# 04-OUTPUT.net
KiCad netlist of a schematic drawn in Altium Designer
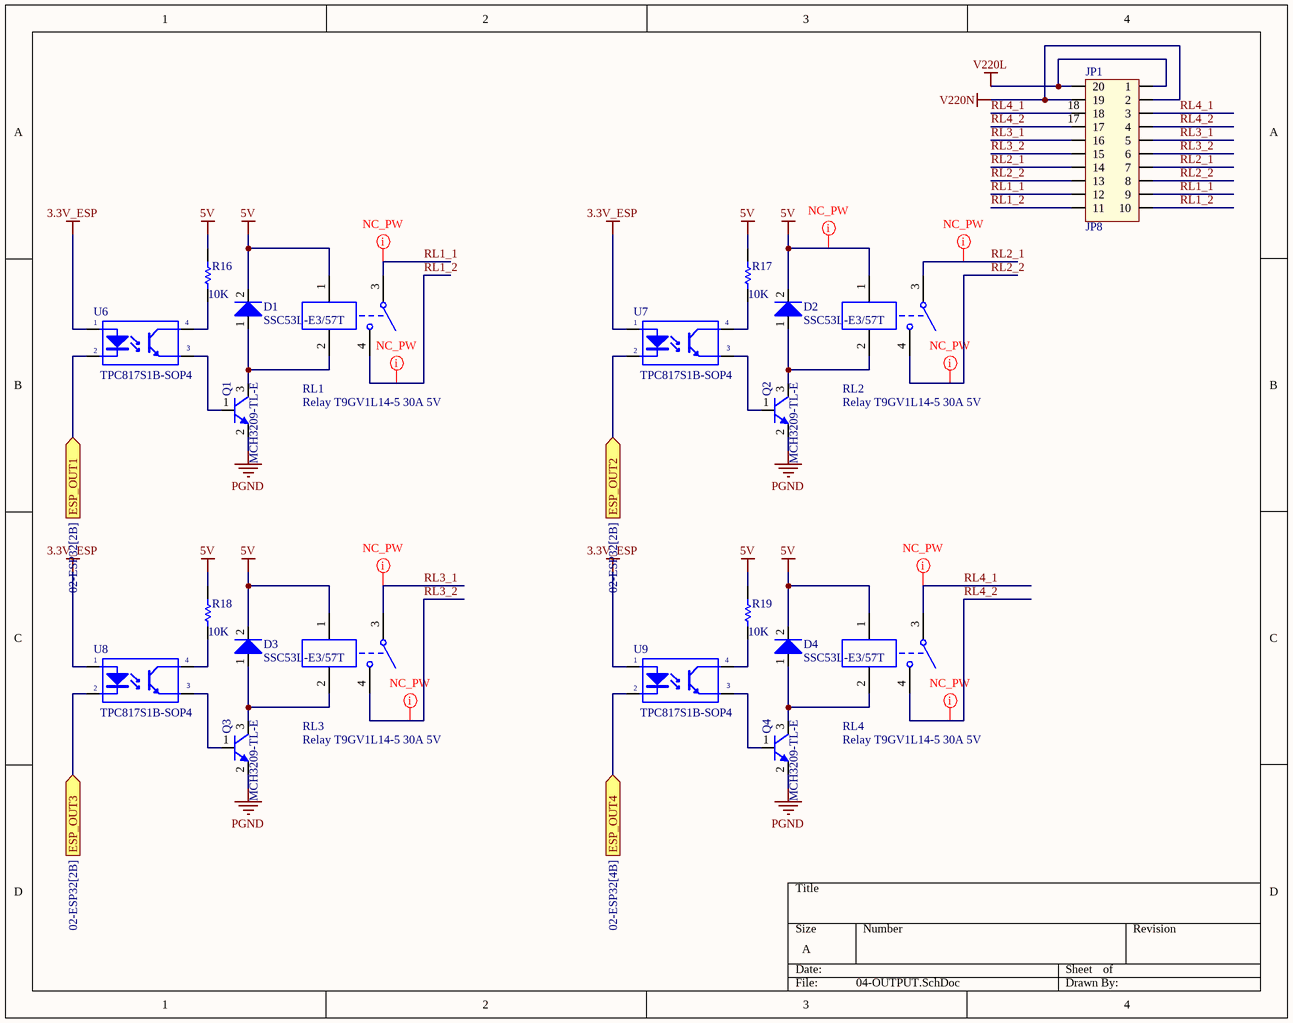
[diagram p0: 04-OUTPUT.SchDoc]

(export (version "E")
  (design (tool "Eeschema 10.0.6"))
  (components
    (comp (ref "D1")
      (value "SSC53L-E3/57T")
      (footprint "1n4007 smd DO214")
      (description "DIODE SCHOTTKY 30V 5A DO214AB")
      (libsource (lib "lpson") (part "10A10"))
    )
    (comp (ref "D2")
      (value "SSC53L-E3/57T")
      (footprint "1n4007 smd DO214")
      (description "DIODE SCHOTTKY 30V 5A DO214AB")
      (libsource (lib "lpson") (part "10A10"))
    )
    (comp (ref "D3")
      (value "SSC53L-E3/57T")
      (footprint "1n4007 smd DO214")
      (description "DIODE SCHOTTKY 30V 5A DO214AB")
      (libsource (lib "lpson") (part "10A10"))
    )
    (comp (ref "D4")
      (value "SSC53L-E3/57T")
      (footprint "1n4007 smd DO214")
      (description "DIODE SCHOTTKY 30V 5A DO214AB")
      (libsource (lib "lpson") (part "10A10"))
    )
    (comp (ref "JP1")
      (value "JP8")
      (footprint "KF142V 10PIN")
      (description "Terminal KF142 9pin")
      (libsource (lib "lpson") (part "Terminal KF142 10pin"))
    )
    (comp (ref "Q1")
      (value "MCH3209-TL-E")
      (footprint "MCH3209-TL-E  SOT-323")
      (description "Bipolar (BJT) Transistor NPN 30V 3A 450MHz 800mW Surface Mount 3-MCPH")
      (libsource (lib "lpson") (part "2SC1815"))
    )
    (comp (ref "Q2")
      (value "MCH3209-TL-E")
      (footprint "MCH3209-TL-E  SOT-323")
      (description "Bipolar (BJT) Transistor NPN 30V 3A 450MHz 800mW Surface Mount 3-MCPH")
      (libsource (lib "lpson") (part "2SC1815"))
    )
    (comp (ref "Q3")
      (value "MCH3209-TL-E")
      (footprint "MCH3209-TL-E  SOT-323")
      (description "Bipolar (BJT) Transistor NPN 30V 3A 450MHz 800mW Surface Mount 3-MCPH")
      (libsource (lib "lpson") (part "2SC1815"))
    )
    (comp (ref "Q4")
      (value "MCH3209-TL-E")
      (footprint "MCH3209-TL-E  SOT-323")
      (description "Bipolar (BJT) Transistor NPN 30V 3A 450MHz 800mW Surface Mount 3-MCPH")
      (libsource (lib "lpson") (part "2SC1815"))
    )
    (comp (ref "R16")
      (value "10K")
      (footprint "Res 0805 SMD")
      (description "RES SMD 249K OHM 1% 1/10W 0805")
      (fields
        (field (name "MANUFACTURER") "Yageo")
        (field (name "MANUFACTURER PART NUMBER") "RC0603FR-07249KL")
      )
      (libsource (lib "GSHT_181013") (part "249K/R0805/1%"))
    )
    (comp (ref "R17")
      (value "10K")
      (footprint "Res 0805 SMD")
      (description "RES SMD 249K OHM 1% 1/10W 0805")
      (fields
        (field (name "MANUFACTURER") "Yageo")
        (field (name "MANUFACTURER PART NUMBER") "RC0603FR-07249KL")
      )
      (libsource (lib "GSHT_181013") (part "249K/R0805/1%"))
    )
    (comp (ref "R18")
      (value "10K")
      (footprint "Res 0805 SMD")
      (description "RES SMD 249K OHM 1% 1/10W 0805")
      (fields
        (field (name "MANUFACTURER") "Yageo")
        (field (name "MANUFACTURER PART NUMBER") "RC0603FR-07249KL")
      )
      (libsource (lib "GSHT_181013") (part "249K/R0805/1%"))
    )
    (comp (ref "R19")
      (value "10K")
      (footprint "Res 0805 SMD")
      (description "RES SMD 249K OHM 1% 1/10W 0805")
      (fields
        (field (name "MANUFACTURER") "Yageo")
        (field (name "MANUFACTURER PART NUMBER") "RC0603FR-07249KL")
      )
      (libsource (lib "GSHT_181013") (part "249K/R0805/1%"))
    )
    (comp (ref "RL1")
      (value "Relay T9GV1L14-5 30A 5V")
      (footprint "RELAY_PA1A_PAN")
      (description "General Purpose Relay SPST-NO (1 Form A) 5VDC Coil Through Hole")
      (libsource (lib "PCB_ESP32_RFID") (part "Relay T9GV1L14-5 30A 5V"))
    )
    (comp (ref "RL2")
      (value "Relay T9GV1L14-5 30A 5V")
      (footprint "RELAY_PA1A_PAN")
      (description "General Purpose Relay SPST-NO (1 Form A) 5VDC Coil Through Hole")
      (libsource (lib "PCB_ESP32_RFID") (part "Relay T9GV1L14-5 30A 5V"))
    )
    (comp (ref "RL3")
      (value "Relay T9GV1L14-5 30A 5V")
      (footprint "RELAY_PA1A_PAN")
      (description "General Purpose Relay SPST-NO (1 Form A) 5VDC Coil Through Hole")
      (libsource (lib "PCB_ESP32_RFID") (part "Relay T9GV1L14-5 30A 5V"))
    )
    (comp (ref "RL4")
      (value "Relay T9GV1L14-5 30A 5V")
      (footprint "RELAY_PA1A_PAN")
      (description "General Purpose Relay SPST-NO (1 Form A) 5VDC Coil Through Hole")
      (libsource (lib "PCB_ESP32_RFID") (part "Relay T9GV1L14-5 30A 5V"))
    )
    (comp (ref "U6")
      (value "TPC817S1B-SOP4")
      (footprint "TPC817-4SOP")
      (description "Optoisolator Transistor Output 5000Vrms 1 Channel 4-SOP")
      (libsource (lib "lpson") (part "PC817"))
    )
    (comp (ref "U7")
      (value "TPC817S1B-SOP4")
      (footprint "TPC817-4SOP")
      (description "Optoisolator Transistor Output 5000Vrms 1 Channel 4-SOP")
      (libsource (lib "lpson") (part "PC817"))
    )
    (comp (ref "U8")
      (value "TPC817S1B-SOP4")
      (footprint "TPC817-4SOP")
      (description "Optoisolator Transistor Output 5000Vrms 1 Channel 4-SOP")
      (libsource (lib "lpson") (part "PC817"))
    )
    (comp (ref "U9")
      (value "TPC817S1B-SOP4")
      (footprint "TPC817-4SOP")
      (description "Optoisolator Transistor Output 5000Vrms 1 Channel 4-SOP")
      (libsource (lib "lpson") (part "PC817"))
    )
  )
  (nets
    (net (code "1") (name "/ESP_OUT1") (class "Default")
      (node (ref "U6") (pin "2") (pinfunction "K_2") (pintype "passive"))
    )
    (net (code "2") (name "/ESP_OUT2") (class "Default")
      (node (ref "U7") (pin "2") (pinfunction "K_2") (pintype "passive"))
    )
    (net (code "3") (name "/ESP_OUT3") (class "Default")
      (node (ref "U8") (pin "2") (pinfunction "K_2") (pintype "passive"))
    )
    (net (code "4") (name "/ESP_OUT4") (class "Default")
      (node (ref "U9") (pin "2") (pinfunction "K_2") (pintype "passive"))
    )
    (net (code "5") (name "/RL1_1") (class "Default")
      (node (ref "JP1") (pin "12") (pinfunction "12_12") (pintype "passive"))
      (node (ref "JP1") (pin "9") (pinfunction "9_9") (pintype "passive"))
      (node (ref "RL1") (pin "3") (pinfunction "3_3") (pintype "passive"))
    )
    (net (code "6") (name "/RL1_2") (class "Default")
      (node (ref "JP1") (pin "10") (pinfunction "10_10") (pintype "passive"))
      (node (ref "JP1") (pin "11") (pinfunction "11_11") (pintype "passive"))
      (node (ref "RL1") (pin "4") (pinfunction "4_4") (pintype "passive"))
    )
    (net (code "7") (name "/RL2_1") (class "Default")
      (node (ref "JP1") (pin "14") (pinfunction "14_14") (pintype "passive"))
      (node (ref "JP1") (pin "7") (pinfunction "7_7") (pintype "passive"))
      (node (ref "RL2") (pin "3") (pinfunction "3_3") (pintype "passive"))
    )
    (net (code "8") (name "/RL2_2") (class "Default")
      (node (ref "JP1") (pin "13") (pinfunction "13_13") (pintype "passive"))
      (node (ref "JP1") (pin "8") (pinfunction "8_8") (pintype "passive"))
      (node (ref "RL2") (pin "4") (pinfunction "4_4") (pintype "passive"))
    )
    (net (code "9") (name "/RL3_1") (class "Default")
      (node (ref "JP1") (pin "16") (pinfunction "16_16") (pintype "passive"))
      (node (ref "JP1") (pin "5") (pinfunction "5_5") (pintype "passive"))
      (node (ref "RL3") (pin "3") (pinfunction "3_3") (pintype "passive"))
    )
    (net (code "10") (name "/RL3_2") (class "Default")
      (node (ref "JP1") (pin "15") (pinfunction "15_15") (pintype "passive"))
      (node (ref "JP1") (pin "6") (pinfunction "6_6") (pintype "passive"))
      (node (ref "RL3") (pin "4") (pinfunction "4_4") (pintype "passive"))
    )
    (net (code "11") (name "/RL4_1") (class "Default")
      (node (ref "JP1") (pin "18") (pinfunction "18_18") (pintype "passive"))
      (node (ref "JP1") (pin "3") (pinfunction "3_3") (pintype "passive"))
      (node (ref "RL4") (pin "3") (pinfunction "3_3") (pintype "passive"))
    )
    (net (code "12") (name "/RL4_2") (class "Default")
      (node (ref "JP1") (pin "17") (pinfunction "17_17") (pintype "passive"))
      (node (ref "JP1") (pin "4") (pinfunction "4_4") (pintype "passive"))
      (node (ref "RL4") (pin "4") (pinfunction "4_4") (pintype "passive"))
    )
    (net (code "13") (name "3.3V_ESP") (class "Default")
      (node (ref "U6") (pin "1") (pinfunction "A_1") (pintype "passive"))
      (node (ref "U7") (pin "1") (pinfunction "A_1") (pintype "passive"))
      (node (ref "U8") (pin "1") (pinfunction "A_1") (pintype "passive"))
      (node (ref "U9") (pin "1") (pinfunction "A_1") (pintype "passive"))
    )
    (net (code "14") (name "5V") (class "Default")
      (node (ref "D1") (pin "2") (pinfunction "K_2") (pintype "passive"))
      (node (ref "D2") (pin "2") (pinfunction "K_2") (pintype "passive"))
      (node (ref "D3") (pin "2") (pinfunction "K_2") (pintype "passive"))
      (node (ref "D4") (pin "2") (pinfunction "K_2") (pintype "passive"))
      (node (ref "R16") (pin "2") (pinfunction "2_2") (pintype "passive"))
      (node (ref "R17") (pin "2") (pinfunction "2_2") (pintype "passive"))
      (node (ref "R18") (pin "2") (pinfunction "2_2") (pintype "passive"))
      (node (ref "R19") (pin "2") (pinfunction "2_2") (pintype "passive"))
      (node (ref "RL1") (pin "1") (pinfunction "1_1") (pintype "passive"))
      (node (ref "RL2") (pin "1") (pinfunction "1_1") (pintype "passive"))
      (node (ref "RL3") (pin "1") (pinfunction "1_1") (pintype "passive"))
      (node (ref "RL4") (pin "1") (pinfunction "1_1") (pintype "passive"))
    )
    (net (code "15") (name "Net-(D1-A)") (class "Default")
      (node (ref "D1") (pin "1") (pinfunction "A_1") (pintype "passive"))
      (node (ref "Q1") (pin "3") (pinfunction "C_3") (pintype "passive"))
      (node (ref "RL1") (pin "2") (pinfunction "2_2") (pintype "passive"))
    )
    (net (code "16") (name "Net-(D2-A)") (class "Default")
      (node (ref "D2") (pin "1") (pinfunction "A_1") (pintype "passive"))
      (node (ref "Q2") (pin "3") (pinfunction "C_3") (pintype "passive"))
      (node (ref "RL2") (pin "2") (pinfunction "2_2") (pintype "passive"))
    )
    (net (code "17") (name "Net-(D3-A)") (class "Default")
      (node (ref "D3") (pin "1") (pinfunction "A_1") (pintype "passive"))
      (node (ref "Q3") (pin "3") (pinfunction "C_3") (pintype "passive"))
      (node (ref "RL3") (pin "2") (pinfunction "2_2") (pintype "passive"))
    )
    (net (code "18") (name "Net-(D4-A)") (class "Default")
      (node (ref "D4") (pin "1") (pinfunction "A_1") (pintype "passive"))
      (node (ref "Q4") (pin "3") (pinfunction "C_3") (pintype "passive"))
      (node (ref "RL4") (pin "2") (pinfunction "2_2") (pintype "passive"))
    )
    (net (code "19") (name "Net-(Q1-B)") (class "Default")
      (node (ref "Q1") (pin "1") (pinfunction "B_1") (pintype "passive"))
      (node (ref "U6") (pin "3") (pinfunction "E_3") (pintype "passive"))
    )
    (net (code "20") (name "Net-(Q2-B)") (class "Default")
      (node (ref "Q2") (pin "1") (pinfunction "B_1") (pintype "passive"))
      (node (ref "U7") (pin "3") (pinfunction "E_3") (pintype "passive"))
    )
    (net (code "21") (name "Net-(Q3-B)") (class "Default")
      (node (ref "Q3") (pin "1") (pinfunction "B_1") (pintype "passive"))
      (node (ref "U8") (pin "3") (pinfunction "E_3") (pintype "passive"))
    )
    (net (code "22") (name "Net-(Q4-B)") (class "Default")
      (node (ref "Q4") (pin "1") (pinfunction "B_1") (pintype "passive"))
      (node (ref "U9") (pin "3") (pinfunction "E_3") (pintype "passive"))
    )
    (net (code "23") (name "Net-(U6-C)") (class "Default")
      (node (ref "R16") (pin "1") (pinfunction "1_1") (pintype "passive"))
      (node (ref "U6") (pin "4") (pinfunction "C_4") (pintype "passive"))
    )
    (net (code "24") (name "Net-(U7-C)") (class "Default")
      (node (ref "R17") (pin "1") (pinfunction "1_1") (pintype "passive"))
      (node (ref "U7") (pin "4") (pinfunction "C_4") (pintype "passive"))
    )
    (net (code "25") (name "Net-(U8-C)") (class "Default")
      (node (ref "R18") (pin "1") (pinfunction "1_1") (pintype "passive"))
      (node (ref "U8") (pin "4") (pinfunction "C_4") (pintype "passive"))
    )
    (net (code "26") (name "Net-(U9-C)") (class "Default")
      (node (ref "R19") (pin "1") (pinfunction "1_1") (pintype "passive"))
      (node (ref "U9") (pin "4") (pinfunction "C_4") (pintype "passive"))
    )
    (net (code "27") (name "PGND") (class "Default")
      (node (ref "Q1") (pin "2") (pinfunction "E_2") (pintype "passive"))
      (node (ref "Q2") (pin "2") (pinfunction "E_2") (pintype "passive"))
      (node (ref "Q3") (pin "2") (pinfunction "E_2") (pintype "passive"))
      (node (ref "Q4") (pin "2") (pinfunction "E_2") (pintype "passive"))
    )
    (net (code "28") (name "V220L") (class "Default")
      (node (ref "JP1") (pin "1") (pinfunction "1_1") (pintype "passive"))
      (node (ref "JP1") (pin "20") (pinfunction "20_20") (pintype "passive"))
    )
    (net (code "29") (name "V220N") (class "Default")
      (node (ref "JP1") (pin "19") (pinfunction "19_19") (pintype "passive"))
      (node (ref "JP1") (pin "2") (pinfunction "2_2") (pintype "passive"))
    )
  )
)
